# DCDC-12V3V5A.net
KiCad netlist of a schematic drawn in EAGLE
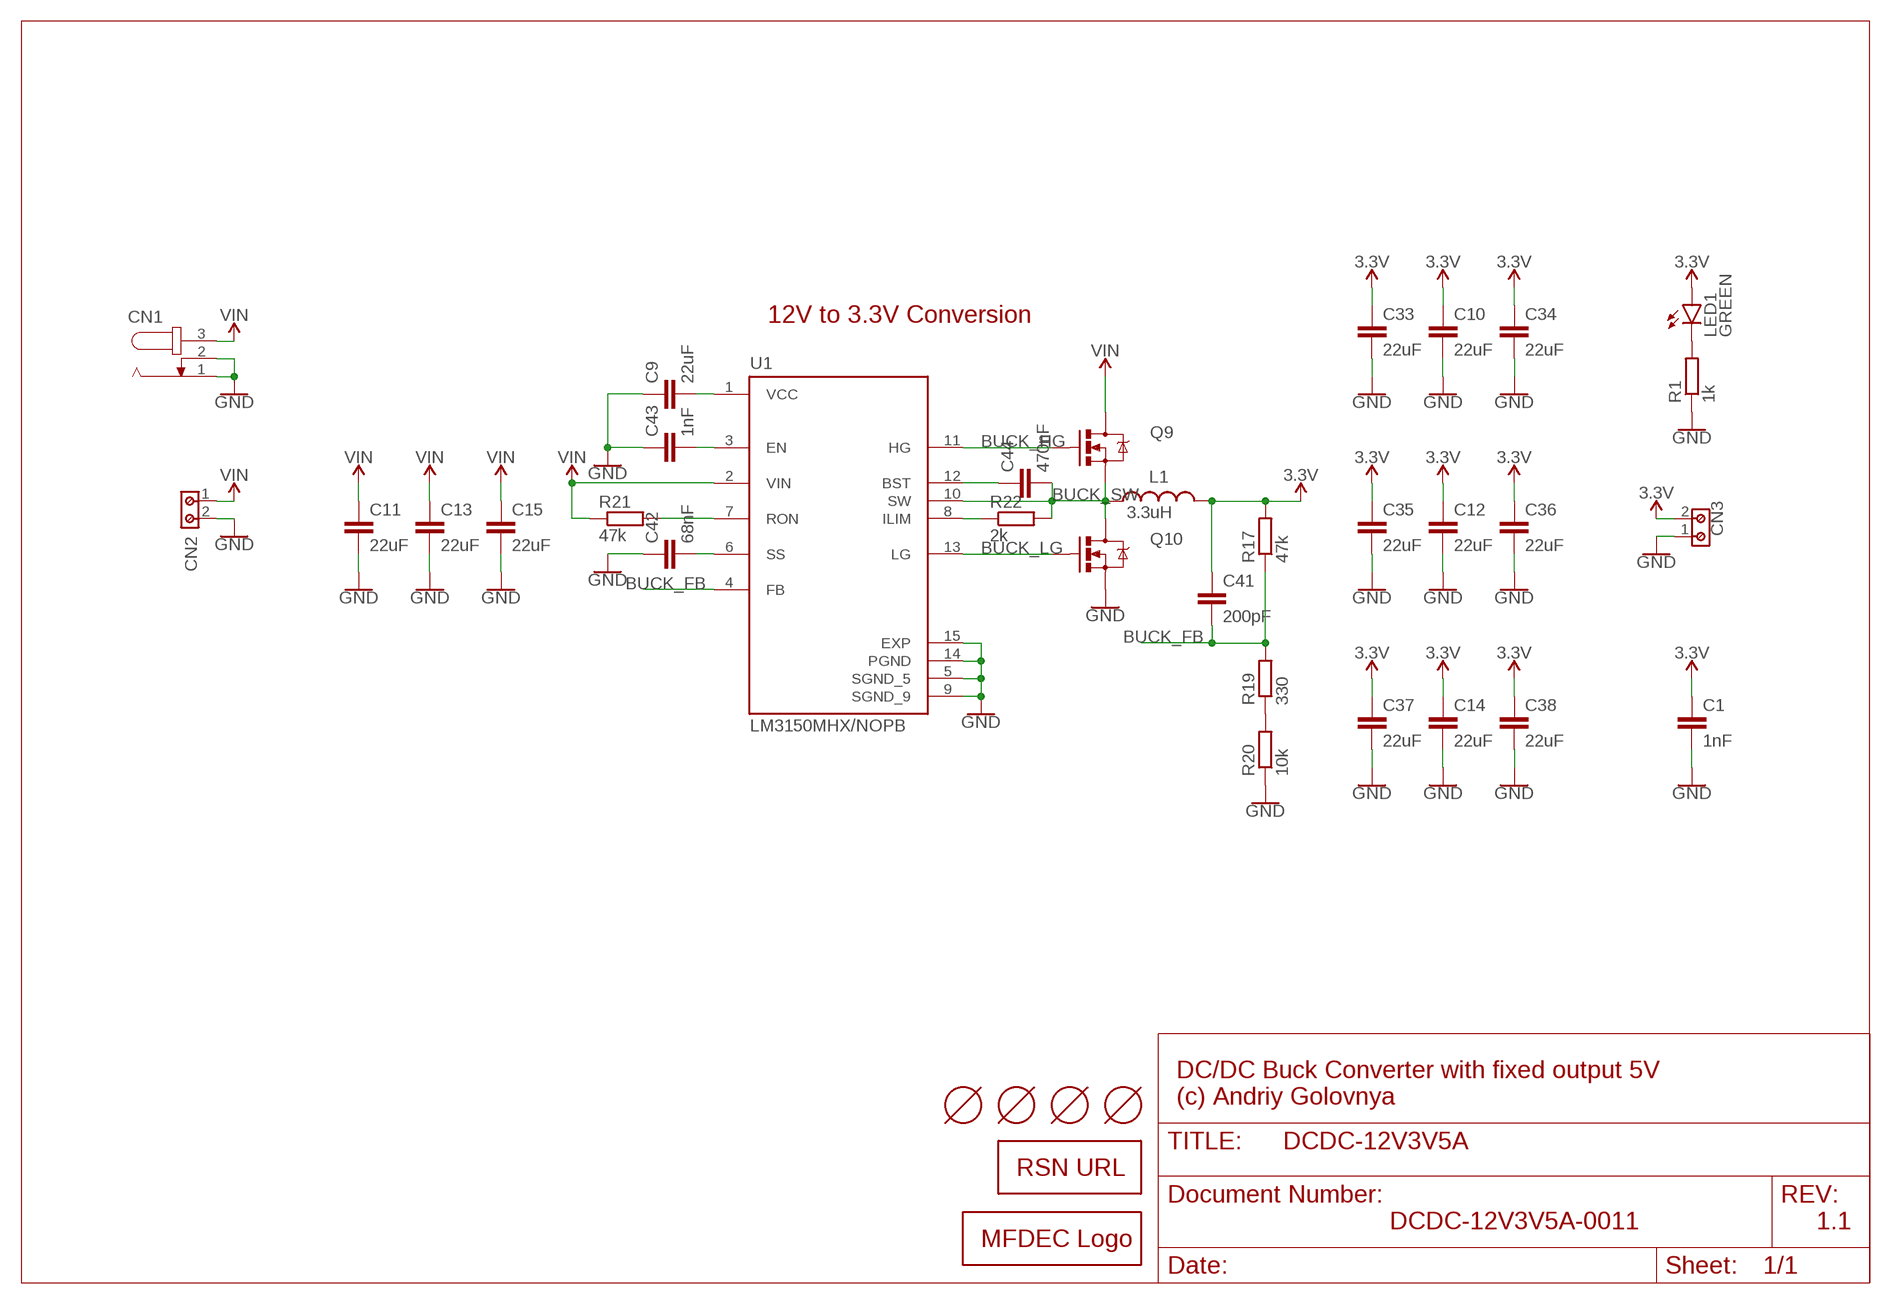
[diagram p0: schematic, sheet 1]

(export (version "E")
  (design (tool "Eeschema 10.0.6"))
  (components
    (comp (ref "C1")
      (value "1nF")
      (footprint "eagle-import:C0603K")
      (libsource (lib "eagle-import") (part "C-EUC0603K"))
    )
    (comp (ref "C9")
      (value "22uF")
      (footprint "eagle-import:C0805K")
      (libsource (lib "eagle-import") (part "C-EUC0805K"))
    )
    (comp (ref "C10")
      (value "22uF")
      (footprint "eagle-import:C0805K")
      (libsource (lib "eagle-import") (part "C-EUC0805K"))
    )
    (comp (ref "C11")
      (value "22uF")
      (footprint "eagle-import:C0805K")
      (libsource (lib "eagle-import") (part "C-EUC0805K"))
    )
    (comp (ref "C12")
      (value "22uF")
      (footprint "eagle-import:C0805K")
      (libsource (lib "eagle-import") (part "C-EUC0805K"))
    )
    (comp (ref "C13")
      (value "22uF")
      (footprint "eagle-import:C0805K")
      (libsource (lib "eagle-import") (part "C-EUC0805K"))
    )
    (comp (ref "C14")
      (value "22uF")
      (footprint "eagle-import:C0805K")
      (libsource (lib "eagle-import") (part "C-EUC0805K"))
    )
    (comp (ref "C15")
      (value "22uF")
      (footprint "eagle-import:C0805K")
      (libsource (lib "eagle-import") (part "C-EUC0805K"))
    )
    (comp (ref "C33")
      (value "22uF")
      (footprint "eagle-import:C0805K")
      (libsource (lib "eagle-import") (part "C-EUC0805K"))
    )
    (comp (ref "C34")
      (value "22uF")
      (footprint "eagle-import:C0805K")
      (libsource (lib "eagle-import") (part "C-EUC0805K"))
    )
    (comp (ref "C35")
      (value "22uF")
      (footprint "eagle-import:C0805K")
      (libsource (lib "eagle-import") (part "C-EUC0805K"))
    )
    (comp (ref "C36")
      (value "22uF")
      (footprint "eagle-import:C0805K")
      (libsource (lib "eagle-import") (part "C-EUC0805K"))
    )
    (comp (ref "C37")
      (value "22uF")
      (footprint "eagle-import:C0805K")
      (libsource (lib "eagle-import") (part "C-EUC0805K"))
    )
    (comp (ref "C38")
      (value "22uF")
      (footprint "eagle-import:C0805K")
      (libsource (lib "eagle-import") (part "C-EUC0805K"))
    )
    (comp (ref "C41")
      (value "200pF")
      (footprint "eagle-import:C0603K")
      (libsource (lib "eagle-import") (part "C-EUC0603K"))
    )
    (comp (ref "C42")
      (value "68nF")
      (footprint "eagle-import:C0603K")
      (libsource (lib "eagle-import") (part "C-EUC0603K"))
    )
    (comp (ref "C43")
      (value "1nF")
      (footprint "eagle-import:C0603K")
      (libsource (lib "eagle-import") (part "C-EUC0603K"))
    )
    (comp (ref "C44")
      (value "470nF")
      (footprint "eagle-import:C0603K")
      (libsource (lib "eagle-import") (part "C-EUC0603K"))
    )
    (comp (ref "CN1")
      (value "JACK-PLUG1")
      (footprint "eagle-import:SPC4078")
      (libsource (lib "eagle-import") (part "JACK-PLUG1"))
    )
    (comp (ref "CN2")
      (value "691213510002")
      (footprint "eagle-import:691213510002")
      (libsource (lib "eagle-import") (part "691213510002"))
    )
    (comp (ref "CN3")
      (value "691213510002")
      (footprint "eagle-import:691213510002")
      (libsource (lib "eagle-import") (part "691213510002"))
    )
    (comp (ref "HOLE1")
      (value "TOOLINGHOLE")
      (footprint "eagle-import:TOOLING-HOLE")
      (libsource (lib "eagle-import") (part "TOOLINGHOLE"))
    )
    (comp (ref "HOLE2")
      (value "TOOLINGHOLE")
      (footprint "eagle-import:TOOLING-HOLE")
      (libsource (lib "eagle-import") (part "TOOLINGHOLE"))
    )
    (comp (ref "HOLE3")
      (value "TOOLINGHOLE")
      (footprint "eagle-import:TOOLING-HOLE")
      (libsource (lib "eagle-import") (part "TOOLINGHOLE"))
    )
    (comp (ref "HOLE4")
      (value "TOOLINGHOLE")
      (footprint "eagle-import:TOOLING-HOLE")
      (libsource (lib "eagle-import") (part "TOOLINGHOLE"))
    )
    (comp (ref "L1")
      (value "3.3uH")
      (footprint "eagle-import:WE-CHSA_1011")
      (libsource (lib "eagle-import") (part "WE-CHSA_1011_7843330330"))
    )
    (comp (ref "LED1")
      (value "GREEN")
      (footprint "eagle-import:SML0603")
      (libsource (lib "eagle-import") (part "LEDSML0603"))
    )
    (comp (ref "LOGO1")
      (value "RSNURL_QR_8MM")
      (footprint "eagle-import:RSNURL_QR_8MM")
      (libsource (lib "eagle-import") (part "RSNURL_QR_8MM"))
    )
    (comp (ref "LOGO2")
      (value "MFDECLOGO_L_10MM")
      (footprint "eagle-import:MFDEC_L_10MM")
      (libsource (lib "eagle-import") (part "MFDECLOGO_L_10MM"))
    )
    (comp (ref "Q9")
      (value "NMOSFET")
      (footprint "eagle-import:DPAK")
      (libsource (lib "eagle-import") (part "MOSFET-NCHANNELFDD8780"))
    )
    (comp (ref "Q10")
      (value "NMOSFET")
      (footprint "eagle-import:DPAK")
      (libsource (lib "eagle-import") (part "MOSFET-NCHANNELFDD8780"))
    )
    (comp (ref "R1")
      (value "1k")
      (footprint "eagle-import:R0603")
      (libsource (lib "eagle-import") (part "R-EU_R0603"))
    )
    (comp (ref "R17")
      (value "47k")
      (footprint "eagle-import:R0603")
      (libsource (lib "eagle-import") (part "R-EU_R0603"))
    )
    (comp (ref "R19")
      (value "330")
      (footprint "eagle-import:R0603")
      (libsource (lib "eagle-import") (part "R-EU_R0603"))
    )
    (comp (ref "R20")
      (value "10k")
      (footprint "eagle-import:R0603")
      (libsource (lib "eagle-import") (part "R-EU_R0603"))
    )
    (comp (ref "R21")
      (value "47k")
      (footprint "eagle-import:R0603")
      (libsource (lib "eagle-import") (part "R-EU_R0603"))
    )
    (comp (ref "R22")
      (value "2k")
      (footprint "eagle-import:R0603")
      (libsource (lib "eagle-import") (part "R-EU_R0603"))
    )
    (comp (ref "U1")
      (value "LM3150MHX/NOPB")
      (footprint "eagle-import:SOP65P640X110-15N")
      (fields (field (name "MF") "Texas Instruments"))
      (libsource (lib "eagle-import") (part "LM3150MHX/NOPB"))
    )
  )
  (nets
    (net (code "1") (name "/BUCK_FB") (class "Default")
      (node (ref "C41") (pin "2") (pinfunction "2_2") (pintype "passive"))
      (node (ref "R17") (pin "1") (pinfunction "1_1") (pintype "passive"))
      (node (ref "R19") (pin "2") (pinfunction "2_2") (pintype "passive"))
      (node (ref "U1") (pin "4") (pinfunction "FB_4") (pintype "input"))
    )
    (net (code "2") (name "/BUCK_HG") (class "Default")
      (node (ref "Q9") (pin "1") (pinfunction "G_1") (pintype "passive"))
      (node (ref "U1") (pin "11") (pinfunction "HG_11") (pintype "output"))
    )
    (net (code "3") (name "/BUCK_LG") (class "Default")
      (node (ref "Q10") (pin "1") (pinfunction "G_1") (pintype "passive"))
      (node (ref "U1") (pin "13") (pinfunction "LG_13") (pintype "output"))
    )
    (net (code "4") (name "/BUCK_SW") (class "Default")
      (node (ref "C44") (pin "2") (pinfunction "2_2") (pintype "passive"))
      (node (ref "L1") (pin "1") (pinfunction "1_1") (pintype "passive"))
      (node (ref "Q10") (pin "4") (pinfunction "D_4") (pintype "passive"))
      (node (ref "Q9") (pin "3") (pinfunction "S_3") (pintype "passive"))
      (node (ref "R22") (pin "2") (pinfunction "2_2") (pintype "passive"))
      (node (ref "U1") (pin "10") (pinfunction "SW_10") (pintype "output"))
    )
    (net (code "5") (name "3.3V") (class "Default")
      (node (ref "C1") (pin "1") (pinfunction "1_1") (pintype "passive"))
      (node (ref "C10") (pin "1") (pinfunction "1_1") (pintype "passive"))
      (node (ref "C12") (pin "1") (pinfunction "1_1") (pintype "passive"))
      (node (ref "C14") (pin "1") (pinfunction "1_1") (pintype "passive"))
      (node (ref "C33") (pin "1") (pinfunction "1_1") (pintype "passive"))
      (node (ref "C34") (pin "1") (pinfunction "1_1") (pintype "passive"))
      (node (ref "C35") (pin "1") (pinfunction "1_1") (pintype "passive"))
      (node (ref "C36") (pin "1") (pinfunction "1_1") (pintype "passive"))
      (node (ref "C37") (pin "1") (pinfunction "1_1") (pintype "passive"))
      (node (ref "C38") (pin "1") (pinfunction "1_1") (pintype "passive"))
      (node (ref "C41") (pin "1") (pinfunction "1_1") (pintype "passive"))
      (node (ref "CN3") (pin "2") (pinfunction "2_2") (pintype "passive"))
      (node (ref "L1") (pin "2") (pinfunction "2_2") (pintype "passive"))
      (node (ref "LED1") (pin "A") (pinfunction "A_A") (pintype "passive"))
      (node (ref "R17") (pin "2") (pinfunction "2_2") (pintype "passive"))
    )
    (net (code "6") (name "GND") (class "Default")
      (node (ref "C1") (pin "2") (pinfunction "2_2") (pintype "passive"))
      (node (ref "C10") (pin "2") (pinfunction "2_2") (pintype "passive"))
      (node (ref "C11") (pin "2") (pinfunction "2_2") (pintype "passive"))
      (node (ref "C12") (pin "2") (pinfunction "2_2") (pintype "passive"))
      (node (ref "C13") (pin "2") (pinfunction "2_2") (pintype "passive"))
      (node (ref "C14") (pin "2") (pinfunction "2_2") (pintype "passive"))
      (node (ref "C15") (pin "2") (pinfunction "2_2") (pintype "passive"))
      (node (ref "C33") (pin "2") (pinfunction "2_2") (pintype "passive"))
      (node (ref "C34") (pin "2") (pinfunction "2_2") (pintype "passive"))
      (node (ref "C35") (pin "2") (pinfunction "2_2") (pintype "passive"))
      (node (ref "C36") (pin "2") (pinfunction "2_2") (pintype "passive"))
      (node (ref "C37") (pin "2") (pinfunction "2_2") (pintype "passive"))
      (node (ref "C38") (pin "2") (pinfunction "2_2") (pintype "passive"))
      (node (ref "C42") (pin "1") (pinfunction "1_1") (pintype "passive"))
      (node (ref "C43") (pin "1") (pinfunction "1_1") (pintype "passive"))
      (node (ref "C9") (pin "1") (pinfunction "1_1") (pintype "passive"))
      (node (ref "CN1") (pin "1") (pinfunction "1_1") (pintype "passive"))
      (node (ref "CN1") (pin "2") (pinfunction "2_2") (pintype "passive"))
      (node (ref "CN2") (pin "2") (pinfunction "2_2") (pintype "passive"))
      (node (ref "CN3") (pin "1") (pinfunction "1_1") (pintype "passive"))
      (node (ref "Q10") (pin "3") (pinfunction "S_3") (pintype "passive"))
      (node (ref "R1") (pin "1") (pinfunction "1_1") (pintype "passive"))
      (node (ref "R20") (pin "1") (pinfunction "1_1") (pintype "passive"))
      (node (ref "U1") (pin "14") (pinfunction "PGND_14") (pintype "power_in"))
      (node (ref "U1") (pin "15") (pinfunction "EXP_15") (pintype "power_in"))
      (node (ref "U1") (pin "5") (pinfunction "SGND_5_5") (pintype "power_in"))
      (node (ref "U1") (pin "9") (pinfunction "SGND_9_9") (pintype "power_in"))
    )
    (net (code "7") (name "Net-(LED1-PadC)") (class "Default")
      (node (ref "LED1") (pin "C") (pinfunction "C_C") (pintype "passive"))
      (node (ref "R1") (pin "2") (pinfunction "2_2") (pintype "passive"))
    )
    (net (code "8") (name "Net-(R19-Pad1)") (class "Default")
      (node (ref "R19") (pin "1") (pinfunction "1_1") (pintype "passive"))
      (node (ref "R20") (pin "2") (pinfunction "2_2") (pintype "passive"))
    )
    (net (code "9") (name "Net-(U1-BST)") (class "Default")
      (node (ref "C44") (pin "1") (pinfunction "1_1") (pintype "passive"))
      (node (ref "U1") (pin "12") (pinfunction "BST_12") (pintype "passive"))
    )
    (net (code "10") (name "Net-(U1-EN)") (class "Default")
      (node (ref "C43") (pin "2") (pinfunction "2_2") (pintype "passive"))
      (node (ref "U1") (pin "3") (pinfunction "EN_3") (pintype "input"))
    )
    (net (code "11") (name "Net-(U1-ILIM)") (class "Default")
      (node (ref "R22") (pin "1") (pinfunction "1_1") (pintype "passive"))
      (node (ref "U1") (pin "8") (pinfunction "ILIM_8") (pintype "passive"))
    )
    (net (code "12") (name "Net-(U1-RON)") (class "Default")
      (node (ref "R21") (pin "2") (pinfunction "2_2") (pintype "passive"))
      (node (ref "U1") (pin "7") (pinfunction "RON_7") (pintype "input"))
    )
    (net (code "13") (name "Net-(U1-SS)") (class "Default")
      (node (ref "C42") (pin "2") (pinfunction "2_2") (pintype "passive"))
      (node (ref "U1") (pin "6") (pinfunction "SS_6") (pintype "input"))
    )
    (net (code "14") (name "Net-(U1-VCC)") (class "Default")
      (node (ref "C9") (pin "2") (pinfunction "2_2") (pintype "passive"))
      (node (ref "U1") (pin "1") (pinfunction "VCC_1") (pintype "power_in"))
    )
    (net (code "15") (name "VIN") (class "Default")
      (node (ref "C11") (pin "1") (pinfunction "1_1") (pintype "passive"))
      (node (ref "C13") (pin "1") (pinfunction "1_1") (pintype "passive"))
      (node (ref "C15") (pin "1") (pinfunction "1_1") (pintype "passive"))
      (node (ref "CN1") (pin "3") (pinfunction "3_3") (pintype "passive"))
      (node (ref "CN2") (pin "1") (pinfunction "1_1") (pintype "passive"))
      (node (ref "Q9") (pin "4") (pinfunction "D_4") (pintype "passive"))
      (node (ref "R21") (pin "1") (pinfunction "1_1") (pintype "passive"))
      (node (ref "U1") (pin "2") (pinfunction "VIN_2") (pintype "input"))
    )
  )
)
